# DC.net
KiCad netlist of a schematic drawn in Altium Designer
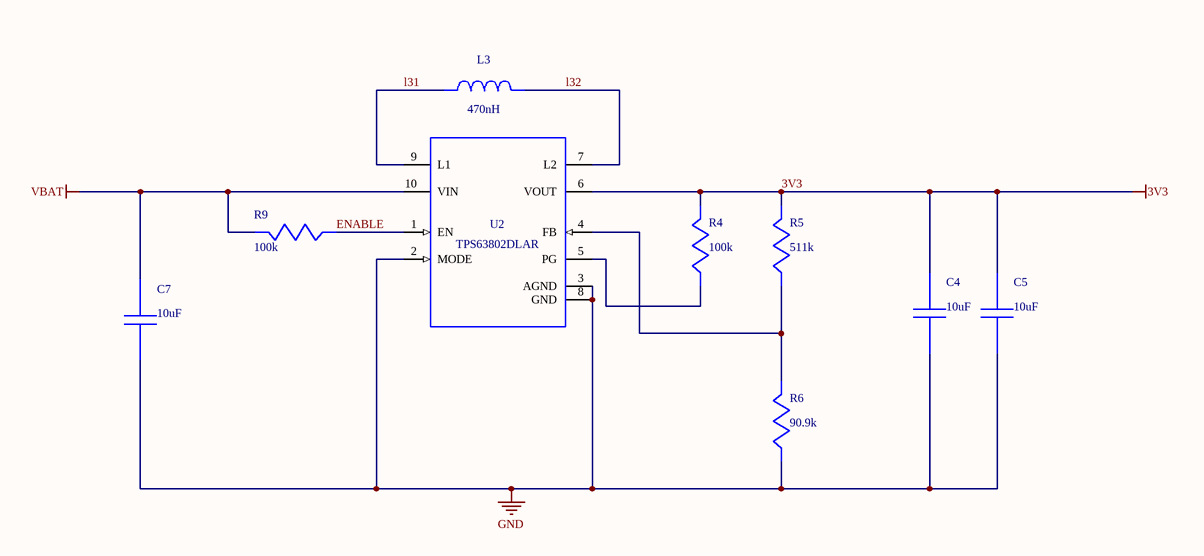
[diagram p0: DC.schdoc]

(export (version "E")
  (design (tool "Eeschema 10.0.6"))
  (components
    (comp (ref "C4")
      (value "10uF")
      (footprint "0603")
      (description "GRM21BR60J226ME3")
      (fields (field (name "MANUFACTURER PART NUMBER") "GRM21BR60J226ME39L"))
      (libsource (lib "TI WEBENCH") (part "Cout"))
    )
    (comp (ref "C5")
      (value "10uF")
      (footprint "0603")
      (description "GRM21BR60J226ME3")
      (fields (field (name "MANUFACTURER PART NUMBER") "GRM21BR60J226ME39L"))
      (libsource (lib "TI WEBENCH") (part "Cout"))
    )
    (comp (ref "C7")
      (value "10uF")
      (footprint "0603")
      (description "CUSTOM1")
      (fields (field (name "MANUFACTURER PART NUMBER") "GENERIC_CAPACITOR"))
      (libsource (lib "TI WEBENCH") (part "Cin"))
    )
    (comp (ref "L3")
      (value "470nH")
      (footprint "0603")
      (description "XEL3520-471ME")
      (libsource (lib "TI WEBENCH") (part "L1"))
    )
    (comp (ref "R4")
      (value "100k")
      (footprint "Lib-Motherboard:0402")
      (description "CRCW0402100KFKED")
      (libsource (lib "TI WEBENCH") (part "Rpg"))
    )
    (comp (ref "R5")
      (value "511k")
      (footprint "Lib-Motherboard:0402")
      (description "CRCW0402511KFKED")
      (libsource (lib "TI WEBENCH") (part "Rfbt"))
    )
    (comp (ref "R6")
      (value "90.9k")
      (footprint "Lib-Motherboard:0402")
      (description "CRCW040290K9FKED")
      (libsource (lib "TI WEBENCH") (part "Rfbb"))
    )
    (comp (ref "R9")
      (value "100k")
      (footprint "Lib-Motherboard:0402")
      (description "CRCW0402100KFKED")
      (libsource (lib "TI WEBENCH") (part "Rpg"))
    )
    (comp (ref "U2")
      (value "TPS63802DLAR")
      (footprint "DLA0010A")
      (fields (field (name "PACKAGEREFERENCE") "TPS63802DLAR"))
      (libsource (lib "TI WEBENCH") (part "U1"))
    )
  )
  (nets
    (net (code "1") (name "/ENABLE") (class "Default")
      (node (ref "R9") (pin "2") (pinfunction "2_2") (pintype "passive"))
      (node (ref "U2") (pin "1") (pinfunction "EN_1") (pintype "input"))
    )
    (net (code "2") (name "/l31") (class "Default")
      (node (ref "L3") (pin "2") (pinfunction "2_2") (pintype "passive"))
      (node (ref "U2") (pin "9") (pinfunction "L1_9") (pintype "passive"))
    )
    (net (code "3") (name "/l32") (class "Default")
      (node (ref "L3") (pin "1") (pinfunction "1_1") (pintype "passive"))
      (node (ref "U2") (pin "7") (pinfunction "L2_7") (pintype "passive"))
    )
    (net (code "4") (name "3V3") (class "Default")
      (node (ref "C4") (pin "1") (pinfunction "1_1") (pintype "passive"))
      (node (ref "C5") (pin "1") (pinfunction "1_1") (pintype "passive"))
      (node (ref "R4") (pin "1") (pinfunction "1_1") (pintype "passive"))
      (node (ref "R5") (pin "1") (pinfunction "1_1") (pintype "passive"))
      (node (ref "U2") (pin "6") (pinfunction "VOUT_6") (pintype "power_in"))
    )
    (net (code "5") (name "GND") (class "Default")
      (node (ref "C4") (pin "2") (pinfunction "2_2") (pintype "passive"))
      (node (ref "C5") (pin "2") (pinfunction "2_2") (pintype "passive"))
      (node (ref "C7") (pin "2") (pinfunction "2_2") (pintype "passive"))
      (node (ref "R6") (pin "2") (pinfunction "2_2") (pintype "passive"))
      (node (ref "U2") (pin "2") (pinfunction "MODE_2") (pintype "input"))
      (node (ref "U2") (pin "3") (pinfunction "AGND_3") (pintype "power_in"))
      (node (ref "U2") (pin "8") (pinfunction "GND_8") (pintype "power_in"))
    )
    (net (code "6") (name "Net-(U2-FB)") (class "Default")
      (node (ref "R5") (pin "2") (pinfunction "2_2") (pintype "passive"))
      (node (ref "R6") (pin "1") (pinfunction "1_1") (pintype "passive"))
      (node (ref "U2") (pin "4") (pinfunction "FB_4") (pintype "input"))
    )
    (net (code "7") (name "Net-(U2-PG)") (class "Default")
      (node (ref "R4") (pin "2") (pinfunction "2_2") (pintype "passive"))
      (node (ref "U2") (pin "5") (pinfunction "PG_5") (pintype "open_collector"))
    )
    (net (code "8") (name "VBAT") (class "Default")
      (node (ref "C7") (pin "1") (pinfunction "1_1") (pintype "passive"))
      (node (ref "R9") (pin "1") (pinfunction "1_1") (pintype "passive"))
      (node (ref "U2") (pin "10") (pinfunction "VIN_10") (pintype "power_in"))
    )
  )
)
